# design.net
KiCad netlist of a schematic drawn in Altium Designer
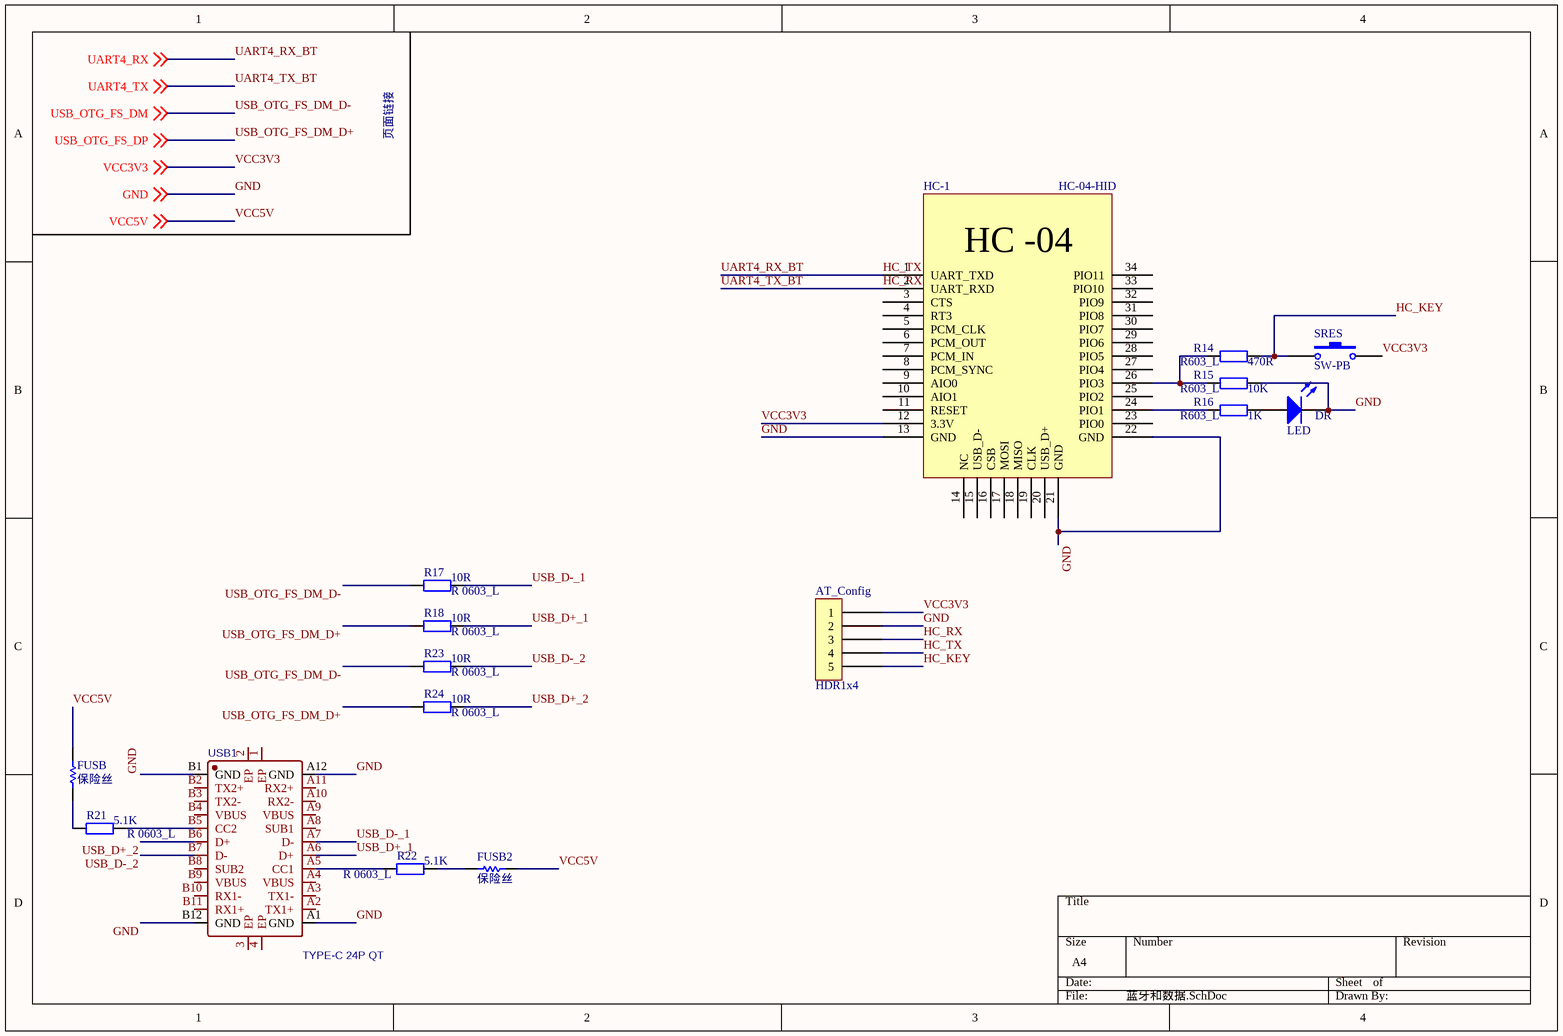
[diagram p0: 蓝牙和数据.SchDoc]

(export (version "E")
  (design (tool "Eeschema 10.0.6"))
  (components
    (comp (ref "AT_Config")
      (value "HDR1x4")
      (footprint "MX 1.25-WS-5P")
      (libsource (lib "Schlib1") (part "HDR1x5_卧"))
    )
    (comp (ref "DR")
      (value "LED")
      (footprint "LED 0805R")
      (description "Typical INFRARED GaAs LED")
      (fields (field (name "PUBLISHER") "Altium Limited"))
      (libsource (lib "Schlib1") (part "LED 0805R 红"))
    )
    (comp (ref "FUSB")
      (value "保险丝")
      (footprint "FU 1206")
      (fields (field (name "PUBLISHER") "Altium Limited"))
      (libsource (lib "Schlib1") (part "FU"))
    )
    (comp (ref "FUSB2")
      (value "保险丝")
      (footprint "FU 1206")
      (fields (field (name "PUBLISHER") "Altium Limited"))
      (libsource (lib "Schlib1") (part "FU"))
    )
    (comp (ref "HC-1") (value "HC-04-HID") (footprint "HC-04") (libsource (lib "Schlib1") (part "HC-04")))
    (comp (ref "R14")
      (value "R603_L")
      (footprint "R 0603_L")
      (description "Resistor")
      (fields (field (name "ALTIUM_VALUE") "470R") (field (name "PUBLISHER") "Altium Limited"))
      (libsource (lib "Schlib1") (part "R 0603_L"))
    )
    (comp (ref "R15")
      (value "R603_L")
      (footprint "R 0603_L")
      (description "Resistor")
      (fields (field (name "ALTIUM_VALUE") "10K") (field (name "PUBLISHER") "Altium Limited"))
      (libsource (lib "Schlib1") (part "R 0603_L"))
    )
    (comp (ref "R16")
      (value "R603_L")
      (footprint "R 0603_L")
      (description "Resistor")
      (fields (field (name "ALTIUM_VALUE") "1K") (field (name "PUBLISHER") "Altium Limited"))
      (libsource (lib "Schlib1") (part "R 0603_L"))
    )
    (comp (ref "R17")
      (value "R 0603_L")
      (footprint "R 0603_L")
      (description "Resistor")
      (fields (field (name "ALTIUM_VALUE") "10R") (field (name "PUBLISHER") "Altium Limited"))
      (libsource (lib "Schlib1") (part "R 0603_L"))
    )
    (comp (ref "R18")
      (value "R 0603_L")
      (footprint "R 0603_L")
      (description "Resistor")
      (fields (field (name "ALTIUM_VALUE") "10R") (field (name "PUBLISHER") "Altium Limited"))
      (libsource (lib "Schlib1") (part "R 0603_L"))
    )
    (comp (ref "R21")
      (value "R 0603_L")
      (footprint "R 0603_L")
      (description "Resistor")
      (fields (field (name "ALTIUM_VALUE") "5.1K") (field (name "PUBLISHER") "Altium Limited"))
      (libsource (lib "Schlib1") (part "R 0603_L"))
    )
    (comp (ref "R22")
      (value "R 0603_L")
      (footprint "R 0603_L")
      (description "Resistor")
      (fields (field (name "ALTIUM_VALUE") "5.1K") (field (name "PUBLISHER") "Altium Limited"))
      (libsource (lib "Schlib1") (part "R 0603_L"))
    )
    (comp (ref "R23")
      (value "R 0603_L")
      (footprint "R 0603_L")
      (description "Resistor")
      (fields (field (name "ALTIUM_VALUE") "10R") (field (name "PUBLISHER") "Altium Limited"))
      (libsource (lib "Schlib1") (part "R 0603_L"))
    )
    (comp (ref "R24")
      (value "R 0603_L")
      (footprint "R 0603_L")
      (description "Resistor")
      (fields (field (name "ALTIUM_VALUE") "10R") (field (name "PUBLISHER") "Altium Limited"))
      (libsource (lib "Schlib1") (part "R 0603_L"))
    )
    (comp (ref "SRES")
      (value "SW-PB")
      (footprint "SMD-3.2*4.2")
      (description "Switch")
      (fields (field (name "PUBLISHER") "Altium Limited"))
      (libsource (lib "Schlib1") (part "SW-PB"))
    )
    (comp (ref "USB1")
      (value "TYPE-C 24P QT")
      (footprint "USB-C-SMD_TYPE-C-24P-QT")
      (fields (field (name "BOM_SUPPLIER PART") "C2681555") (field (name "CONTRIBUTOR") "LCSC"))
      (libsource (lib "Schlib1") (part "TYPE-C 24P QT"))
    )
  )
  (nets
    (net (code "1") (name "/HC_KEY") (class "Default")
      (node (ref "AT_Config") (pin "5") (pinfunction "5_5") (pintype "passive"))
      (node (ref "R14") (pin "2") (pinfunction "2_2") (pintype "passive"))
      (node (ref "SRES") (pin "1") (pinfunction "1_1") (pintype "passive"))
    )
    (net (code "2") (name "/USB_D+_1") (class "Default")
      (node (ref "R18") (pin "2") (pinfunction "2_2") (pintype "passive"))
      (node (ref "USB1") (pin "A6") (pinfunction "D+_A6") (pintype "passive"))
    )
    (net (code "3") (name "/USB_D+_2") (class "Default")
      (node (ref "R24") (pin "2") (pinfunction "2_2") (pintype "passive"))
      (node (ref "USB1") (pin "B6") (pinfunction "D+_B6") (pintype "passive"))
    )
    (net (code "4") (name "/USB_D-_1") (class "Default")
      (node (ref "R17") (pin "2") (pinfunction "2_2") (pintype "passive"))
      (node (ref "USB1") (pin "A7") (pinfunction "D-_A7") (pintype "passive"))
    )
    (net (code "5") (name "/USB_D-_2") (class "Default")
      (node (ref "R23") (pin "2") (pinfunction "2_2") (pintype "passive"))
      (node (ref "USB1") (pin "B7") (pinfunction "D-_B7") (pintype "passive"))
    )
    (net (code "6") (name "GND") (class "Default")
      (node (ref "AT_Config") (pin "2") (pinfunction "2_2") (pintype "passive"))
      (node (ref "DR") (pin "2") (pinfunction "K_2") (pintype "passive"))
      (node (ref "HC-1") (pin "13") (pinfunction "GND_13") (pintype "passive"))
      (node (ref "HC-1") (pin "21") (pinfunction "GND_21") (pintype "passive"))
      (node (ref "HC-1") (pin "22") (pinfunction "GND_22") (pintype "passive"))
      (node (ref "R15") (pin "2") (pinfunction "2_2") (pintype "passive"))
      (node (ref "USB1") (pin "A1") (pinfunction "GND_A1") (pintype "passive"))
      (node (ref "USB1") (pin "A12") (pinfunction "GND_A12") (pintype "passive"))
      (node (ref "USB1") (pin "B1") (pinfunction "GND_B1") (pintype "passive"))
      (node (ref "USB1") (pin "B12") (pinfunction "GND_B12") (pintype "passive"))
    )
    (net (code "7") (name "Net-(DR-A)") (class "Default")
      (node (ref "DR") (pin "1") (pinfunction "A_1") (pintype "passive"))
      (node (ref "R16") (pin "2") (pinfunction "2_2") (pintype "passive"))
    )
    (net (code "8") (name "Net-(FUSB-Pad2)") (class "Default")
      (node (ref "FUSB") (pin "2") (pinfunction "2_2") (pintype "passive"))
      (node (ref "R21") (pin "1") (pinfunction "1_1") (pintype "passive"))
    )
    (net (code "9") (name "Net-(FUSB2-Pad1)") (class "Default")
      (node (ref "FUSB2") (pin "1") (pinfunction "1_1") (pintype "passive"))
      (node (ref "R22") (pin "2") (pinfunction "2_2") (pintype "passive"))
    )
    (net (code "10") (name "Net-(HC-1-PIO1)") (class "Default")
      (node (ref "HC-1") (pin "24") (pinfunction "PIO1_24") (pintype "passive"))
      (node (ref "R16") (pin "1") (pinfunction "1_1") (pintype "passive"))
    )
    (net (code "11") (name "Net-(HC-1-PIO3)") (class "Default")
      (node (ref "HC-1") (pin "26") (pinfunction "PIO3_26") (pintype "passive"))
      (node (ref "R14") (pin "1") (pinfunction "1_1") (pintype "passive"))
      (node (ref "R15") (pin "1") (pinfunction "1_1") (pintype "passive"))
    )
    (net (code "12") (name "Net-(USB1-CC1)") (class "Default")
      (node (ref "R22") (pin "1") (pinfunction "1_1") (pintype "passive"))
      (node (ref "USB1") (pin "A5") (pinfunction "CC1_A5") (pintype "passive"))
    )
    (net (code "13") (name "Net-(USB1-CC2)") (class "Default")
      (node (ref "R21") (pin "2") (pinfunction "2_2") (pintype "passive"))
      (node (ref "USB1") (pin "B5") (pinfunction "CC2_B5") (pintype "passive"))
    )
    (net (code "14") (name "UART4_RX") (class "Default")
      (node (ref "AT_Config") (pin "4") (pinfunction "4_4") (pintype "passive"))
      (node (ref "HC-1") (pin "1") (pinfunction "UART_TXD_1") (pintype "passive"))
    )
    (net (code "15") (name "UART4_TX") (class "Default")
      (node (ref "AT_Config") (pin "3") (pinfunction "3_3") (pintype "passive"))
      (node (ref "HC-1") (pin "2") (pinfunction "UART_RXD_2") (pintype "passive"))
    )
    (net (code "16") (name "USB_OTG_FS_DM") (class "Default")
      (node (ref "R17") (pin "1") (pinfunction "1_1") (pintype "passive"))
      (node (ref "R23") (pin "1") (pinfunction "1_1") (pintype "passive"))
    )
    (net (code "17") (name "USB_OTG_FS_DP") (class "Default")
      (node (ref "R18") (pin "1") (pinfunction "1_1") (pintype "passive"))
      (node (ref "R24") (pin "1") (pinfunction "1_1") (pintype "passive"))
    )
    (net (code "18") (name "VCC3V3") (class "Default")
      (node (ref "AT_Config") (pin "1") (pinfunction "1_1") (pintype "passive"))
      (node (ref "HC-1") (pin "12") (pinfunction "3.3V_12") (pintype "passive"))
      (node (ref "SRES") (pin "2") (pinfunction "2_2") (pintype "passive"))
    )
    (net (code "19") (name "VCC5V") (class "Default")
      (node (ref "FUSB") (pin "1") (pinfunction "1_1") (pintype "passive"))
      (node (ref "FUSB2") (pin "2") (pinfunction "2_2") (pintype "passive"))
    )
    (net (code "20") (name "unconnected-(HC-1-AIO0-Pad9)") (class "Default")
      (node (ref "HC-1") (pin "9") (pinfunction "AIO0_9") (pintype "passive"))
    )
    (net (code "21") (name "unconnected-(HC-1-AIO1-Pad10)") (class "Default")
      (node (ref "HC-1") (pin "10") (pinfunction "AIO1_10") (pintype "passive"))
    )
    (net (code "22") (name "unconnected-(HC-1-CLK-Pad19)") (class "Default")
      (node (ref "HC-1") (pin "19") (pinfunction "CLK_19") (pintype "passive"))
    )
    (net (code "23") (name "unconnected-(HC-1-CSB-Pad16)") (class "Default")
      (node (ref "HC-1") (pin "16") (pinfunction "CSB_16") (pintype "passive"))
    )
    (net (code "24") (name "unconnected-(HC-1-CTS-Pad3)") (class "Default")
      (node (ref "HC-1") (pin "3") (pinfunction "CTS_3") (pintype "passive"))
    )
    (net (code "25") (name "unconnected-(HC-1-MISO-Pad18)") (class "Default")
      (node (ref "HC-1") (pin "18") (pinfunction "MISO_18") (pintype "passive"))
    )
    (net (code "26") (name "unconnected-(HC-1-MOSI-Pad17)") (class "Default")
      (node (ref "HC-1") (pin "17") (pinfunction "MOSI_17") (pintype "passive"))
    )
    (net (code "27") (name "unconnected-(HC-1-NC-Pad14)") (class "Default")
      (node (ref "HC-1") (pin "14") (pinfunction "NC_14") (pintype "passive"))
    )
    (net (code "28") (name "unconnected-(HC-1-PCM_CLK-Pad5)") (class "Default")
      (node (ref "HC-1") (pin "5") (pinfunction "PCM_CLK_5") (pintype "passive"))
    )
    (net (code "29") (name "unconnected-(HC-1-PCM_IN-Pad7)") (class "Default")
      (node (ref "HC-1") (pin "7") (pinfunction "PCM_IN_7") (pintype "passive"))
    )
    (net (code "30") (name "unconnected-(HC-1-PCM_OUT-Pad6)") (class "Default")
      (node (ref "HC-1") (pin "6") (pinfunction "PCM_OUT_6") (pintype "passive"))
    )
    (net (code "31") (name "unconnected-(HC-1-PCM_SYNC-Pad8)") (class "Default")
      (node (ref "HC-1") (pin "8") (pinfunction "PCM_SYNC_8") (pintype "passive"))
    )
    (net (code "32") (name "unconnected-(HC-1-PIO0-Pad23)") (class "Default")
      (node (ref "HC-1") (pin "23") (pinfunction "PIO0_23") (pintype "passive"))
    )
    (net (code "33") (name "unconnected-(HC-1-PIO2-Pad25)") (class "Default")
      (node (ref "HC-1") (pin "25") (pinfunction "PIO2_25") (pintype "passive"))
    )
    (net (code "34") (name "unconnected-(HC-1-PIO4-Pad27)") (class "Default")
      (node (ref "HC-1") (pin "27") (pinfunction "PIO4_27") (pintype "passive"))
    )
    (net (code "35") (name "unconnected-(HC-1-PIO5-Pad28)") (class "Default")
      (node (ref "HC-1") (pin "28") (pinfunction "PIO5_28") (pintype "passive"))
    )
    (net (code "36") (name "unconnected-(HC-1-PIO6-Pad29)") (class "Default")
      (node (ref "HC-1") (pin "29") (pinfunction "PIO6_29") (pintype "passive"))
    )
    (net (code "37") (name "unconnected-(HC-1-PIO7-Pad30)") (class "Default")
      (node (ref "HC-1") (pin "30") (pinfunction "PIO7_30") (pintype "passive"))
    )
    (net (code "38") (name "unconnected-(HC-1-PIO8-Pad31)") (class "Default")
      (node (ref "HC-1") (pin "31") (pinfunction "PIO8_31") (pintype "passive"))
    )
    (net (code "39") (name "unconnected-(HC-1-PIO9-Pad32)") (class "Default")
      (node (ref "HC-1") (pin "32") (pinfunction "PIO9_32") (pintype "passive"))
    )
    (net (code "40") (name "unconnected-(HC-1-PIO10-Pad33)") (class "Default")
      (node (ref "HC-1") (pin "33") (pinfunction "PIO10_33") (pintype "passive"))
    )
    (net (code "41") (name "unconnected-(HC-1-PIO11-Pad34)") (class "Default")
      (node (ref "HC-1") (pin "34") (pinfunction "PIO11_34") (pintype "passive"))
    )
    (net (code "42") (name "unconnected-(HC-1-RESET-Pad11)") (class "Default")
      (node (ref "HC-1") (pin "11") (pinfunction "RESET_11") (pintype "passive"))
    )
    (net (code "43") (name "unconnected-(HC-1-RT3-Pad4)") (class "Default")
      (node (ref "HC-1") (pin "4") (pinfunction "RT3_4") (pintype "passive"))
    )
    (net (code "44") (name "unconnected-(HC-1-USB_D+-Pad20)") (class "Default")
      (node (ref "HC-1") (pin "20") (pinfunction "USB_D+_20") (pintype "passive"))
    )
    (net (code "45") (name "unconnected-(HC-1-USB_D--Pad15)") (class "Default")
      (node (ref "HC-1") (pin "15") (pinfunction "USB_D-_15") (pintype "passive"))
    )
    (net (code "46") (name "unconnected-(USB1-EP-Pad1)") (class "Default")
      (node (ref "USB1") (pin "1") (pinfunction "EP_1") (pintype "passive"))
    )
    (net (code "47") (name "unconnected-(USB1-EP-Pad2)") (class "Default")
      (node (ref "USB1") (pin "2") (pinfunction "EP_2") (pintype "passive"))
    )
    (net (code "48") (name "unconnected-(USB1-EP-Pad3)") (class "Default")
      (node (ref "USB1") (pin "3") (pinfunction "EP_3") (pintype "passive"))
    )
    (net (code "49") (name "unconnected-(USB1-EP-Pad4)") (class "Default")
      (node (ref "USB1") (pin "4") (pinfunction "EP_4") (pintype "passive"))
    )
    (net (code "50") (name "unconnected-(USB1-RX1+-PadB11)") (class "Default")
      (node (ref "USB1") (pin "B11") (pinfunction "RX1+_B11") (pintype "passive"))
    )
    (net (code "51") (name "unconnected-(USB1-RX1--PadB10)") (class "Default")
      (node (ref "USB1") (pin "B10") (pinfunction "RX1-_B10") (pintype "passive"))
    )
    (net (code "52") (name "unconnected-(USB1-RX2+-PadA11)") (class "Default")
      (node (ref "USB1") (pin "A11") (pinfunction "RX2+_A11") (pintype "passive"))
    )
    (net (code "53") (name "unconnected-(USB1-RX2--PadA10)") (class "Default")
      (node (ref "USB1") (pin "A10") (pinfunction "RX2-_A10") (pintype "passive"))
    )
    (net (code "54") (name "unconnected-(USB1-SUB1-PadA8)") (class "Default")
      (node (ref "USB1") (pin "A8") (pinfunction "SUB1_A8") (pintype "passive"))
    )
    (net (code "55") (name "unconnected-(USB1-SUB2-PadB8)") (class "Default")
      (node (ref "USB1") (pin "B8") (pinfunction "SUB2_B8") (pintype "passive"))
    )
    (net (code "56") (name "unconnected-(USB1-TX1+-PadA2)") (class "Default")
      (node (ref "USB1") (pin "A2") (pinfunction "TX1+_A2") (pintype "passive"))
    )
    (net (code "57") (name "unconnected-(USB1-TX1--PadA3)") (class "Default")
      (node (ref "USB1") (pin "A3") (pinfunction "TX1-_A3") (pintype "passive"))
    )
    (net (code "58") (name "unconnected-(USB1-TX2+-PadB2)") (class "Default")
      (node (ref "USB1") (pin "B2") (pinfunction "TX2+_B2") (pintype "passive"))
    )
    (net (code "59") (name "unconnected-(USB1-TX2--PadB3)") (class "Default")
      (node (ref "USB1") (pin "B3") (pinfunction "TX2-_B3") (pintype "passive"))
    )
    (net (code "60") (name "unconnected-(USB1-VBUS-PadA4)") (class "Default")
      (node (ref "USB1") (pin "A4") (pinfunction "VBUS_A4") (pintype "passive"))
    )
    (net (code "61") (name "unconnected-(USB1-VBUS-PadA9)") (class "Default")
      (node (ref "USB1") (pin "A9") (pinfunction "VBUS_A9") (pintype "passive"))
    )
    (net (code "62") (name "unconnected-(USB1-VBUS-PadB4)") (class "Default")
      (node (ref "USB1") (pin "B4") (pinfunction "VBUS_B4") (pintype "passive"))
    )
    (net (code "63") (name "unconnected-(USB1-VBUS-PadB9)") (class "Default")
      (node (ref "USB1") (pin "B9") (pinfunction "VBUS_B9") (pintype "passive"))
    )
  )
)
